# new_inverter.net
KiCad netlist of a schematic drawn in EAGLE
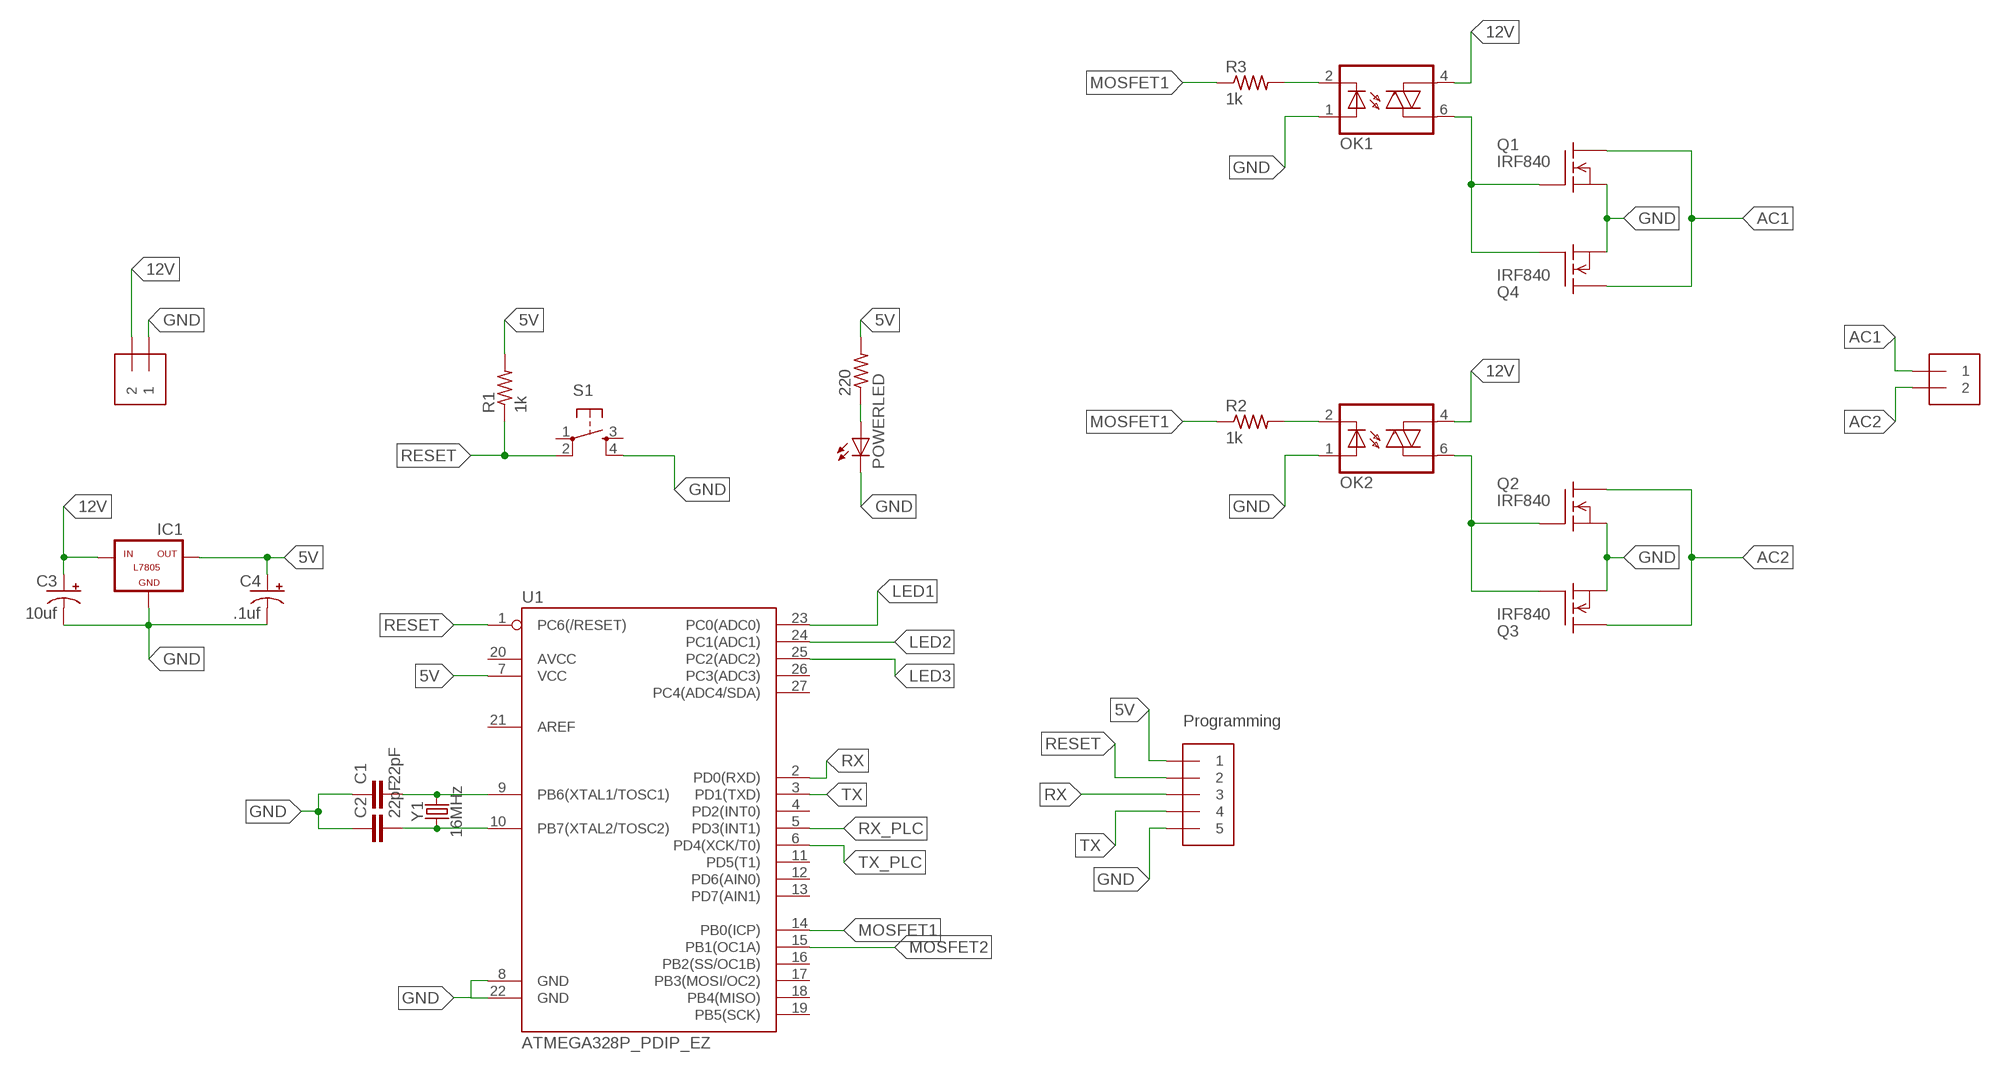
[diagram p0: schematic, sheet 1]

(export (version "E")
  (design (tool "Eeschema 10.0.6"))
  (components
    (comp (ref "220")
      (value "R-US_0204/5")
      (footprint "eagle-import:0204_5")
      (libsource (lib "eagle-import") (part "R-US_0204/5"))
    )
    (comp (ref "C1")
      (value "22pF")
      (footprint "eagle-import:CAP-PTH-2.54")
      (libsource (lib "eagle-import") (part "22PF-PTH-2.54MM-200V-5%"))
    )
    (comp (ref "C2")
      (value "22pF")
      (footprint "eagle-import:CAP-PTH-2.54")
      (libsource (lib "eagle-import") (part "22PF-PTH-2.54MM-200V-5%"))
    )
    (comp (ref "C3")
      (value "10uf")
      (footprint "eagle-import:E5-5")
      (libsource (lib "eagle-import") (part "CPOL-USE5-5"))
    )
    (comp (ref "C4")
      (value ".1uf")
      (footprint "eagle-import:E5-5")
      (libsource (lib "eagle-import") (part "CPOL-USE5-5"))
    )
    (comp (ref "IC1")
      (value "L7805")
      (footprint "eagle-import:78XXL")
      (libsource (lib "eagle-import") (part "L7805"))
    )
    (comp (ref "J1")
      (value "1X2-3.5MM")
      (footprint "eagle-import:1X2-3.5MM")
      (libsource (lib "eagle-import") (part "1X2-3.5MM"))
    )
    (comp (ref "J2")
      (value "1X5")
      (footprint "eagle-import:1X05-3.5MM")
      (libsource (lib "eagle-import") (part "1X5"))
    )
    (comp (ref "J3")
      (value "1X2-3.5MM")
      (footprint "eagle-import:1X2-3.5MM")
      (libsource (lib "eagle-import") (part "1X2-3.5MM"))
    )
    (comp (ref "OK1")
      (value "MOC3021M")
      (footprint "eagle-import:DIL06")
      (libsource (lib "eagle-import") (part "MOC30M21"))
    )
    (comp (ref "OK2")
      (value "MOC3021M")
      (footprint "eagle-import:DIL06")
      (libsource (lib "eagle-import") (part "MOC30M21"))
    )
    (comp (ref "POWERLED")
      (value "LED5MM")
      (footprint "eagle-import:LED5MM")
      (libsource (lib "eagle-import") (part "LED5MM"))
    )
    (comp (ref "Q1")
      (value "IRF840")
      (footprint "eagle-import:TO220")
      (libsource (lib "eagle-import") (part "IRF840"))
    )
    (comp (ref "Q2")
      (value "IRF840")
      (footprint "eagle-import:TO220")
      (libsource (lib "eagle-import") (part "IRF840"))
    )
    (comp (ref "Q3")
      (value "IRF840")
      (footprint "eagle-import:TO220")
      (libsource (lib "eagle-import") (part "IRF840"))
    )
    (comp (ref "Q4")
      (value "IRF840")
      (footprint "eagle-import:TO220")
      (libsource (lib "eagle-import") (part "IRF840"))
    )
    (comp (ref "R1")
      (value "1k")
      (footprint "eagle-import:0204_5")
      (libsource (lib "eagle-import") (part "R-US_0204/5"))
    )
    (comp (ref "R2")
      (value "1k")
      (footprint "eagle-import:0204_5")
      (libsource (lib "eagle-import") (part "R-US_0204/5"))
    )
    (comp (ref "R3")
      (value "1k")
      (footprint "eagle-import:0204_5")
      (libsource (lib "eagle-import") (part "R-US_0204/5"))
    )
    (comp (ref "S1")
      (value "TAC_SWITCHPTH")
      (footprint "eagle-import:TACTILE-PTH")
      (libsource (lib "eagle-import") (part "TAC_SWITCHPTH"))
    )
    (comp (ref "U1")
      (value "ATMEGA328P_PDIP_EZ")
      (footprint "eagle-import:DIP28-SIMON-KIT")
      (libsource (lib "eagle-import") (part "ATMEGA328P_PDIP_EZ"))
    )
    (comp (ref "Y1")
      (value "16MHz")
      (footprint "eagle-import:HC49US")
      (libsource (lib "eagle-import") (part "CRYSTAL-16MHZPTH-HC49US"))
    )
  )
  (nets
    (net (code "1") (name "5V") (class "Default")
      (node (ref "220") (pin "2") (pinfunction "2_2") (pintype "passive"))
      (node (ref "C4") (pin "+") (pinfunction "+_+") (pintype "passive"))
      (node (ref "IC1") (pin "OUT") (pinfunction "OUT_OUT") (pintype "passive"))
      (node (ref "J2") (pin "1") (pinfunction "1_1") (pintype "passive"))
      (node (ref "R1") (pin "2") (pinfunction "2_2") (pintype "passive"))
      (node (ref "U1") (pin "7") (pinfunction "VCC_7") (pintype "bidirectional"))
    )
    (net (code "2") (name "12V") (class "Default")
      (node (ref "C3") (pin "+") (pinfunction "+_+") (pintype "passive"))
      (node (ref "IC1") (pin "IN") (pinfunction "IN_IN") (pintype "input"))
      (node (ref "J1") (pin "2") (pinfunction "2_2") (pintype "passive"))
      (node (ref "OK1") (pin "4") (pinfunction "A1_4") (pintype "passive"))
      (node (ref "OK2") (pin "4") (pinfunction "A1_4") (pintype "passive"))
    )
    (net (code "3") (name "AC1") (class "Default")
      (node (ref "J3") (pin "1") (pinfunction "1_1") (pintype "passive"))
      (node (ref "Q1") (pin "2") (pinfunction "D_2") (pintype "passive"))
      (node (ref "Q4") (pin "2") (pinfunction "D_2") (pintype "passive"))
    )
    (net (code "4") (name "AC2") (class "Default")
      (node (ref "J3") (pin "2") (pinfunction "2_2") (pintype "passive"))
      (node (ref "Q2") (pin "2") (pinfunction "D_2") (pintype "passive"))
      (node (ref "Q3") (pin "2") (pinfunction "D_2") (pintype "passive"))
    )
    (net (code "5") (name "GND") (class "Default")
      (node (ref "C1") (pin "1") (pinfunction "1_1") (pintype "passive"))
      (node (ref "C2") (pin "1") (pinfunction "1_1") (pintype "passive"))
      (node (ref "C3") (pin "-") (pinfunction "-_-") (pintype "passive"))
      (node (ref "C4") (pin "-") (pinfunction "-_-") (pintype "passive"))
      (node (ref "IC1") (pin "GND") (pinfunction "GND_GND") (pintype "input"))
      (node (ref "J1") (pin "1") (pinfunction "1_1") (pintype "passive"))
      (node (ref "J2") (pin "5") (pinfunction "5_5") (pintype "passive"))
      (node (ref "OK1") (pin "1") (pinfunction "A_1") (pintype "passive"))
      (node (ref "OK2") (pin "1") (pinfunction "A_1") (pintype "passive"))
      (node (ref "POWERLED") (pin "K") (pinfunction "C_K") (pintype "passive"))
      (node (ref "Q1") (pin "3") (pinfunction "S_3") (pintype "passive"))
      (node (ref "Q2") (pin "3") (pinfunction "S_3") (pintype "passive"))
      (node (ref "Q3") (pin "3") (pinfunction "S_3") (pintype "passive"))
      (node (ref "Q4") (pin "3") (pinfunction "S_3") (pintype "passive"))
      (node (ref "S1") (pin "4") (pinfunction "4_4") (pintype "passive"))
      (node (ref "U1") (pin "22") (pinfunction "GND_22") (pintype "bidirectional"))
      (node (ref "U1") (pin "8") (pinfunction "GND_8") (pintype "bidirectional"))
    )
    (net (code "6") (name "LED1") (class "Default")
      (node (ref "U1") (pin "23") (pinfunction "PC0(ADC0)_23") (pintype "bidirectional"))
    )
    (net (code "7") (name "LED2") (class "Default")
      (node (ref "U1") (pin "24") (pinfunction "PC1(ADC1)_24") (pintype "bidirectional"))
    )
    (net (code "8") (name "LED3") (class "Default")
      (node (ref "U1") (pin "25") (pinfunction "PC2(ADC2)_25") (pintype "bidirectional"))
    )
    (net (code "9") (name "MOSFET1") (class "Default")
      (node (ref "R2") (pin "1") (pinfunction "1_1") (pintype "passive"))
      (node (ref "R3") (pin "1") (pinfunction "1_1") (pintype "passive"))
      (node (ref "U1") (pin "14") (pinfunction "PB0(ICP)_14") (pintype "bidirectional"))
    )
    (net (code "10") (name "MOSFET2") (class "Default")
      (node (ref "U1") (pin "15") (pinfunction "PB1(OC1A)_15") (pintype "bidirectional"))
    )
    (net (code "11") (name "Net-(220-Pad1)") (class "Default")
      (node (ref "220") (pin "1") (pinfunction "1_1") (pintype "passive"))
      (node (ref "POWERLED") (pin "A") (pinfunction "A_A") (pintype "passive"))
    )
    (net (code "12") (name "Net-(OK1-A2)") (class "Default")
      (node (ref "OK1") (pin "6") (pinfunction "A2_6") (pintype "passive"))
      (node (ref "Q1") (pin "1") (pinfunction "G_1") (pintype "passive"))
      (node (ref "Q4") (pin "1") (pinfunction "G_1") (pintype "passive"))
    )
    (net (code "13") (name "Net-(OK1-C)") (class "Default")
      (node (ref "OK1") (pin "2") (pinfunction "C_2") (pintype "passive"))
      (node (ref "R3") (pin "2") (pinfunction "2_2") (pintype "passive"))
    )
    (net (code "14") (name "Net-(OK2-A2)") (class "Default")
      (node (ref "OK2") (pin "6") (pinfunction "A2_6") (pintype "passive"))
      (node (ref "Q2") (pin "1") (pinfunction "G_1") (pintype "passive"))
      (node (ref "Q3") (pin "1") (pinfunction "G_1") (pintype "passive"))
    )
    (net (code "15") (name "Net-(OK2-C)") (class "Default")
      (node (ref "OK2") (pin "2") (pinfunction "C_2") (pintype "passive"))
      (node (ref "R2") (pin "2") (pinfunction "2_2") (pintype "passive"))
    )
    (net (code "16") (name "Net-(U1-PB6(XTAL1{slash}TOSC1))") (class "Default")
      (node (ref "C1") (pin "2") (pinfunction "2_2") (pintype "passive"))
      (node (ref "U1") (pin "9") (pinfunction "PB6(XTAL1/TOSC1)_9") (pintype "bidirectional"))
      (node (ref "Y1") (pin "2") (pinfunction "2_2") (pintype "passive"))
    )
    (net (code "17") (name "Net-(U1-PB7(XTAL2{slash}TOSC2))") (class "Default")
      (node (ref "C2") (pin "2") (pinfunction "2_2") (pintype "passive"))
      (node (ref "U1") (pin "10") (pinfunction "PB7(XTAL2/TOSC2)_10") (pintype "bidirectional"))
      (node (ref "Y1") (pin "1") (pinfunction "1_1") (pintype "passive"))
    )
    (net (code "18") (name "RESET") (class "Default")
      (node (ref "J2") (pin "2") (pinfunction "2_2") (pintype "passive"))
      (node (ref "R1") (pin "1") (pinfunction "1_1") (pintype "passive"))
      (node (ref "S1") (pin "2") (pinfunction "2_2") (pintype "passive"))
      (node (ref "U1") (pin "1") (pinfunction "PC6(/RESET)_1") (pintype "bidirectional"))
    )
    (net (code "19") (name "RX") (class "Default")
      (node (ref "J2") (pin "3") (pinfunction "3_3") (pintype "passive"))
      (node (ref "U1") (pin "2") (pinfunction "PD0(RXD)_2") (pintype "bidirectional"))
    )
    (net (code "20") (name "RX_PLC") (class "Default")
      (node (ref "U1") (pin "5") (pinfunction "PD3(INT1)_5") (pintype "bidirectional"))
    )
    (net (code "21") (name "TX") (class "Default")
      (node (ref "J2") (pin "4") (pinfunction "4_4") (pintype "passive"))
      (node (ref "U1") (pin "3") (pinfunction "PD1(TXD)_3") (pintype "bidirectional"))
    )
    (net (code "22") (name "TX_PLC") (class "Default")
      (node (ref "U1") (pin "6") (pinfunction "PD4(XCK/T0)_6") (pintype "bidirectional"))
    )
    (net (code "23") (name "unconnected-(S1-Pad1)") (class "Default")
      (node (ref "S1") (pin "1") (pinfunction "1_1") (pintype "passive"))
    )
    (net (code "24") (name "unconnected-(S1-Pad3)") (class "Default")
      (node (ref "S1") (pin "3") (pinfunction "3_3") (pintype "passive"))
    )
    (net (code "25") (name "unconnected-(U1-AREF-Pad21)") (class "Default")
      (node (ref "U1") (pin "21") (pinfunction "AREF_21") (pintype "bidirectional"))
    )
    (net (code "26") (name "unconnected-(U1-AVCC-Pad20)") (class "Default")
      (node (ref "U1") (pin "20") (pinfunction "AVCC_20") (pintype "bidirectional"))
    )
    (net (code "27") (name "unconnected-(U1-PB2(SS{slash}OC1B)-Pad16)") (class "Default")
      (node (ref "U1") (pin "16") (pinfunction "PB2(SS/OC1B)_16") (pintype "bidirectional"))
    )
    (net (code "28") (name "unconnected-(U1-PB3(MOSI{slash}OC2)-Pad17)") (class "Default")
      (node (ref "U1") (pin "17") (pinfunction "PB3(MOSI/OC2)_17") (pintype "bidirectional"))
    )
    (net (code "29") (name "unconnected-(U1-PB4(MISO)-Pad18)") (class "Default")
      (node (ref "U1") (pin "18") (pinfunction "PB4(MISO)_18") (pintype "bidirectional"))
    )
    (net (code "30") (name "unconnected-(U1-PB5(SCK)-Pad19)") (class "Default")
      (node (ref "U1") (pin "19") (pinfunction "PB5(SCK)_19") (pintype "bidirectional"))
    )
    (net (code "31") (name "unconnected-(U1-PC3(ADC3)-Pad26)") (class "Default")
      (node (ref "U1") (pin "26") (pinfunction "PC3(ADC3)_26") (pintype "bidirectional"))
    )
    (net (code "32") (name "unconnected-(U1-PC4(ADC4{slash}SDA)-Pad27)") (class "Default")
      (node (ref "U1") (pin "27") (pinfunction "PC4(ADC4/SDA)_27") (pintype "bidirectional"))
    )
    (net (code "33") (name "unconnected-(U1-PD2(INT0)-Pad4)") (class "Default")
      (node (ref "U1") (pin "4") (pinfunction "PD2(INT0)_4") (pintype "bidirectional"))
    )
    (net (code "34") (name "unconnected-(U1-PD5(T1)-Pad11)") (class "Default")
      (node (ref "U1") (pin "11") (pinfunction "PD5(T1)_11") (pintype "bidirectional"))
    )
    (net (code "35") (name "unconnected-(U1-PD6(AIN0)-Pad12)") (class "Default")
      (node (ref "U1") (pin "12") (pinfunction "PD6(AIN0)_12") (pintype "bidirectional"))
    )
    (net (code "36") (name "unconnected-(U1-PD7(AIN1)-Pad13)") (class "Default")
      (node (ref "U1") (pin "13") (pinfunction "PD7(AIN1)_13") (pintype "bidirectional"))
    )
  )
)
